# lcd.net
KiCad netlist of a schematic drawn in EAGLE
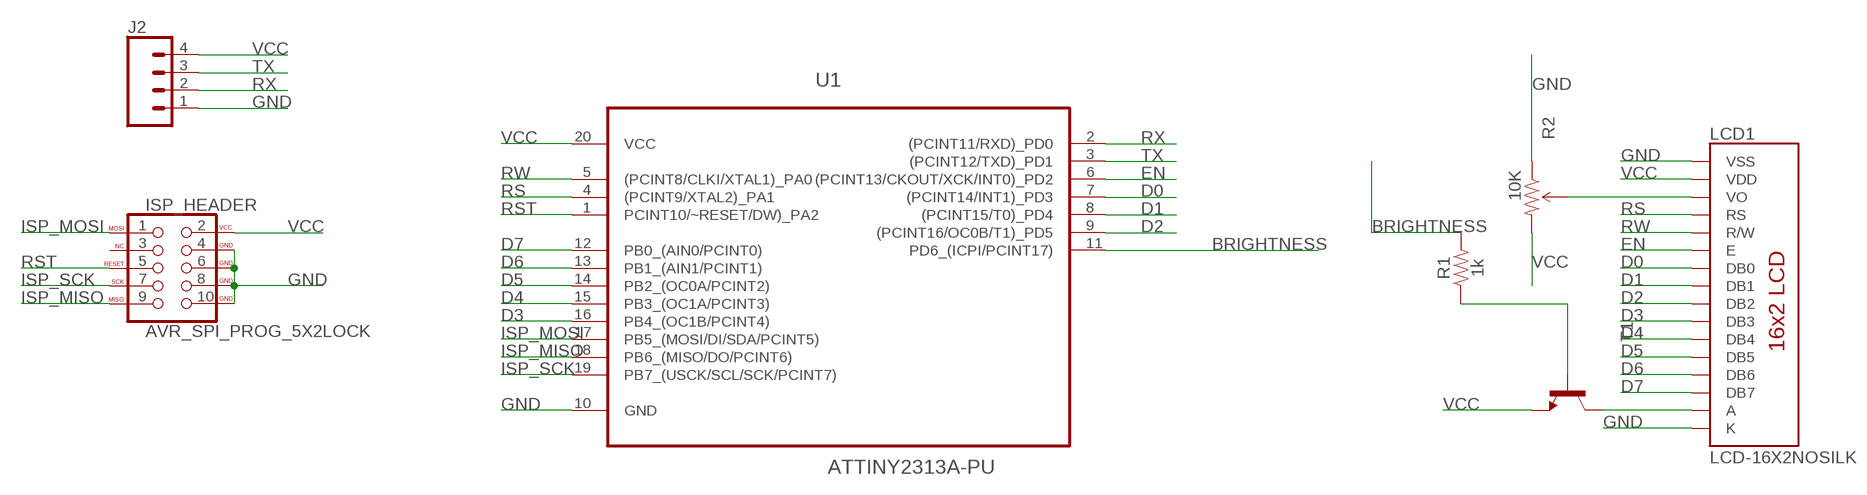
[diagram p0: schematic, sheet 1]

(export (version "E")
  (design (tool "Eeschema 10.0.6"))
  (components
    (comp (ref "ISP_HEADER")
      (value "AVR_SPI_PROG_5X2LOCK")
      (footprint "eagle-import:2X5-SHROUDED_LOCK")
      (libsource (lib "eagle-import") (part "AVR_SPI_PROG_5X2LOCK"))
    )
    (comp (ref "J2")
      (value "CONN_04")
      (footprint "eagle-import:1X04")
      (libsource (lib "eagle-import") (part "CONN_04"))
    )
    (comp (ref "LCD1")
      (value "LCD-16X2NOSILK")
      (footprint "eagle-import:LCD-16X2_NOSILK")
      (libsource (lib "eagle-import") (part "LCD-16X2NOSILK"))
    )
    (comp (ref "R1")
      (value "1k")
      (footprint "eagle-import:AXIAL-0.3")
      (libsource (lib "eagle-import") (part "1KOHM-HORIZ-1/4W-5%"))
    )
    (comp (ref "R2")
      (value "10K")
      (footprint "eagle-import:TRIM_POT_PTH")
      (libsource (lib "eagle-import") (part "TRIMPOTPTH"))
    )
    (comp (ref "T1")
      (value "-NPN-TO92-ECB")
      (footprint "eagle-import:TO92-ECB")
      (libsource (lib "eagle-import") (part "-NPN-TO92-ECB"))
    )
    (comp (ref "U1")
      (value "ATTINY2313A-PU")
      (footprint "eagle-import:DIP254P762X533-20")
      (libsource (lib "eagle-import") (part "ATTINY2313A-PU"))
    )
  )
  (nets
    (net (code "1") (name "/BRIGHTNESS") (class "Default")
      (node (ref "R1") (pin "P$2") (pinfunction "2_P$2") (pintype "passive"))
      (node (ref "U1") (pin "11") (pinfunction "PD6_(ICPI/PCINT17)_11") (pintype "bidirectional"))
    )
    (net (code "2") (name "/D0") (class "Default")
      (node (ref "LCD1") (pin "7") (pinfunction "DB0_7") (pintype "bidirectional"))
      (node (ref "U1") (pin "7") (pinfunction "(PCINT14/INT1)_PD3_7") (pintype "bidirectional"))
    )
    (net (code "3") (name "/D1") (class "Default")
      (node (ref "LCD1") (pin "8") (pinfunction "DB1_8") (pintype "bidirectional"))
      (node (ref "U1") (pin "8") (pinfunction "(PCINT15/T0)_PD4_8") (pintype "bidirectional"))
    )
    (net (code "4") (name "/D2") (class "Default")
      (node (ref "LCD1") (pin "9") (pinfunction "DB2_9") (pintype "bidirectional"))
      (node (ref "U1") (pin "9") (pinfunction "(PCINT16/OC0B/T1)_PD5_9") (pintype "bidirectional"))
    )
    (net (code "5") (name "/D3") (class "Default")
      (node (ref "LCD1") (pin "10") (pinfunction "DB3_10") (pintype "bidirectional"))
      (node (ref "U1") (pin "16") (pinfunction "PB4_(OC1B/PCINT4)_16") (pintype "bidirectional"))
    )
    (net (code "6") (name "/D4") (class "Default")
      (node (ref "LCD1") (pin "11") (pinfunction "DB4_11") (pintype "bidirectional"))
      (node (ref "U1") (pin "15") (pinfunction "PB3_(OC1A/PCINT3)_15") (pintype "bidirectional"))
    )
    (net (code "7") (name "/D5") (class "Default")
      (node (ref "LCD1") (pin "12") (pinfunction "DB5_12") (pintype "bidirectional"))
      (node (ref "U1") (pin "14") (pinfunction "PB2_(OC0A/PCINT2)_14") (pintype "bidirectional"))
    )
    (net (code "8") (name "/D6") (class "Default")
      (node (ref "LCD1") (pin "13") (pinfunction "DB6_13") (pintype "bidirectional"))
      (node (ref "U1") (pin "13") (pinfunction "PB1_(AIN1/PCINT1)_13") (pintype "bidirectional"))
    )
    (net (code "9") (name "/D7") (class "Default")
      (node (ref "LCD1") (pin "14") (pinfunction "DB7_14") (pintype "bidirectional"))
      (node (ref "U1") (pin "12") (pinfunction "PB0_(AIN0/PCINT0)_12") (pintype "bidirectional"))
    )
    (net (code "10") (name "/EN") (class "Default")
      (node (ref "LCD1") (pin "6") (pinfunction "E_6") (pintype "input"))
      (node (ref "U1") (pin "6") (pinfunction "(PCINT13/CKOUT/XCK/INT0)_PD2_6") (pintype "bidirectional"))
    )
    (net (code "11") (name "/GND") (class "Default")
      (node (ref "ISP_HEADER") (pin "10") (pinfunction "GND_10") (pintype "power_in"))
      (node (ref "ISP_HEADER") (pin "4") (pinfunction "GND_4") (pintype "power_in"))
      (node (ref "ISP_HEADER") (pin "6") (pinfunction "GND_6") (pintype "power_in"))
      (node (ref "ISP_HEADER") (pin "8") (pinfunction "GND_8") (pintype "power_in"))
      (node (ref "J2") (pin "1") (pinfunction "1_1") (pintype "passive"))
      (node (ref "LCD1") (pin "1") (pinfunction "VSS_1") (pintype "power_in"))
      (node (ref "LCD1") (pin "16") (pinfunction "K_16") (pintype "power_in"))
      (node (ref "R2") (pin "1") (pinfunction "CCW_1") (pintype "passive"))
      (node (ref "U1") (pin "10") (pinfunction "GND_10") (pintype "passive"))
    )
    (net (code "12") (name "/ISP_MISO") (class "Default")
      (node (ref "ISP_HEADER") (pin "9") (pinfunction "MISO_9") (pintype "passive"))
      (node (ref "U1") (pin "18") (pinfunction "PB6_(MISO/DO/PCINT6)_18") (pintype "bidirectional"))
    )
    (net (code "13") (name "/ISP_MOSI") (class "Default")
      (node (ref "ISP_HEADER") (pin "1") (pinfunction "MOSI_1") (pintype "passive"))
      (node (ref "U1") (pin "17") (pinfunction "PB5_(MOSI/DI/SDA/PCINT5)_17") (pintype "bidirectional"))
    )
    (net (code "14") (name "/ISP_SCK") (class "Default")
      (node (ref "ISP_HEADER") (pin "7") (pinfunction "SCK_7") (pintype "passive"))
      (node (ref "U1") (pin "19") (pinfunction "PB7_(USCK/SCL/SCK/PCINT7)_19") (pintype "bidirectional"))
    )
    (net (code "15") (name "/RS") (class "Default")
      (node (ref "LCD1") (pin "4") (pinfunction "RS_4") (pintype "input"))
      (node (ref "U1") (pin "4") (pinfunction "(PCINT9/XTAL2)_PA1_4") (pintype "bidirectional"))
    )
    (net (code "16") (name "/RST") (class "Default")
      (node (ref "ISP_HEADER") (pin "5") (pinfunction "RESET_5") (pintype "passive"))
      (node (ref "U1") (pin "1") (pinfunction "PCINT10/~{RESET/DW})_PA2_1") (pintype "bidirectional"))
    )
    (net (code "17") (name "/RW") (class "Default")
      (node (ref "LCD1") (pin "5") (pinfunction "R/W_5") (pintype "input"))
      (node (ref "U1") (pin "5") (pinfunction "(PCINT8/CLKI/XTAL1)_PA0_5") (pintype "bidirectional"))
    )
    (net (code "18") (name "/RX") (class "Default")
      (node (ref "J2") (pin "2") (pinfunction "2_2") (pintype "passive"))
      (node (ref "U1") (pin "2") (pinfunction "(PCINT11/RXD)_PD0_2") (pintype "bidirectional"))
    )
    (net (code "19") (name "/TX") (class "Default")
      (node (ref "J2") (pin "3") (pinfunction "3_3") (pintype "passive"))
      (node (ref "U1") (pin "3") (pinfunction "(PCINT12/TXD)_PD1_3") (pintype "bidirectional"))
    )
    (net (code "20") (name "/VCC") (class "Default")
      (node (ref "ISP_HEADER") (pin "2") (pinfunction "VCC_2") (pintype "power_in"))
      (node (ref "J2") (pin "4") (pinfunction "4_4") (pintype "passive"))
      (node (ref "LCD1") (pin "2") (pinfunction "VDD_2") (pintype "power_in"))
      (node (ref "R2") (pin "3") (pinfunction "CW_3") (pintype "passive"))
      (node (ref "T1") (pin "E") (pinfunction "E_E") (pintype "passive"))
      (node (ref "U1") (pin "20") (pinfunction "VCC_20") (pintype "power_in"))
    )
    (net (code "21") (name "Net-(LCD1-A)") (class "Default")
      (node (ref "LCD1") (pin "15") (pinfunction "A_15") (pintype "power_in"))
      (node (ref "T1") (pin "C") (pinfunction "C_C") (pintype "passive"))
    )
    (net (code "22") (name "Net-(LCD1-VO)") (class "Default")
      (node (ref "LCD1") (pin "3") (pinfunction "VO_3") (pintype "bidirectional"))
      (node (ref "R2") (pin "2") (pinfunction "WIPER_2") (pintype "passive"))
    )
    (net (code "23") (name "Net-(R1-1)") (class "Default")
      (node (ref "R1") (pin "P$1") (pinfunction "1_P$1") (pintype "passive"))
      (node (ref "T1") (pin "B") (pinfunction "B_B") (pintype "passive"))
    )
    (net (code "24") (name "unconnected-(ISP_HEADER-NC-Pad3)") (class "Default")
      (node (ref "ISP_HEADER") (pin "3") (pinfunction "NC_3") (pintype "no_connect"))
    )
  )
)
